# 5.net
KiCad netlist of a schematic drawn in Altium Designer
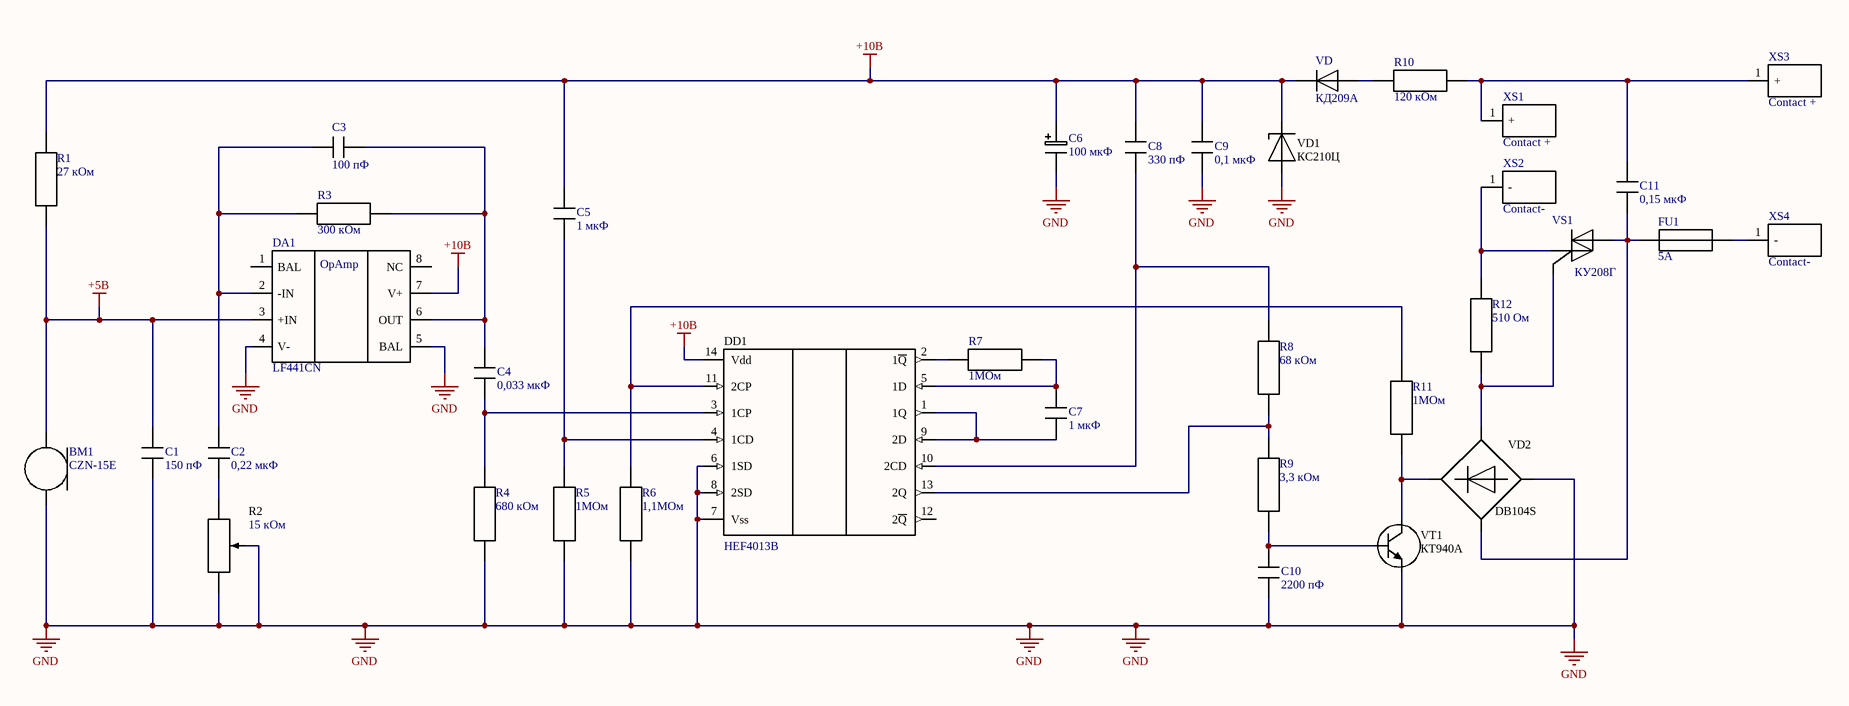
[diagram p0: 5 лист.SchDoc]

(export (version "E")
  (design (tool "Eeschema 10.0.6"))
  (components
    (comp (ref "BM1")
      (value "CZN-15E")
      (footprint "CZN-15E")
      (description "Microphone")
      (libsource (lib "Schlib1") (part "CZN-15E"))
    )
    (comp (ref "C1")
      (value "150 пФ")
      (footprint "CAP: 0805")
      (description "Capacitor Unpolarized")
      (fields (field (name "Comment") "CAP 0805 150 пФ"))
      (libsource (lib "Schlib1") (part "CAP 0805 150 пФ"))
    )
    (comp (ref "C2")
      (value "0,22 мкФ")
      (footprint "CAP: 0805")
      (description "Capacitor Unpolarized")
      (fields (field (name "Comment") "CAP 0805 0,22 мкФ"))
      (libsource (lib "Schlib1") (part "CAP 0805 0,22 мкФ"))
    )
    (comp (ref "C3")
      (value "100 пФ")
      (footprint "CAP: 0805")
      (description "Capacitor Unpolarized")
      (fields (field (name "Comment") "CAP 0805 100 пФ"))
      (libsource (lib "Schlib1") (part "CAP 0805 100 пФ"))
    )
    (comp (ref "C4")
      (value "0,033 мкФ")
      (footprint "CAP: 0805")
      (description "Capacitor Unpolarized")
      (fields (field (name "Comment") "CAP 0805 0,033 мкФ"))
      (libsource (lib "Schlib1") (part "CAP 0805 0,033 мкФ"))
    )
    (comp (ref "C5")
      (value "1 мкФ")
      (footprint "CAP: 0805")
      (description "Capacitor Unpolarized")
      (fields (field (name "Comment") "CAP 0805 1 мкФ"))
      (libsource (lib "Schlib1") (part "CAP 0805 1 мкФ"))
    )
    (comp (ref "C6")
      (value "100 мкФ")
      (footprint "ECAP 6,3x5.4мм")
      (description "Capacitor Polarized")
      (fields (field (name "Comment") "CAP 6,3X5.4 100 мкФ"))
      (libsource (lib "Schlib1") (part "CAP 6,3X5.4 100 мкФ"))
    )
    (comp (ref "C7")
      (value "1 мкФ")
      (footprint "CAP: 0805")
      (description "Capacitor Unpolarized")
      (fields (field (name "Comment") "CAP 0805 1 мкФ"))
      (libsource (lib "Schlib1") (part "CAP 0805 1 мкФ"))
    )
    (comp (ref "C8")
      (value "330 пФ")
      (footprint "CAP: 0805")
      (description "Capacitor Unpolarized")
      (fields (field (name "Comment") "CAP 0805 330 пФ"))
      (libsource (lib "Schlib1") (part "CAP 0805 330 пФ"))
    )
    (comp (ref "C9")
      (value "0,1 мкФ")
      (footprint "K73-17 B32521")
      (description "Capacitor Unpolarized")
      (fields (field (name "Comment") "CAP K73-17 0,1 мкФ"))
      (libsource (lib "Schlib1") (part "CAP K73-17 0,1 мкФ"))
    )
    (comp (ref "C10")
      (value "2200 пФ")
      (footprint "CAP: 0805")
      (description "Capacitor Unpolarized")
      (fields (field (name "Comment") "CAP 0805 2200 пФ"))
      (libsource (lib "Schlib1") (part "CAP 0805 2200 пФ"))
    )
    (comp (ref "C11")
      (value "0,15 мкФ")
      (footprint "CAP: 1206")
      (description "Capacitor Unpolarized")
      (fields (field (name "Comment") "CAP 1206 0,15 мкФ"))
      (libsource (lib "Schlib1") (part "CAP 1206 0,15 мкФ"))
    )
    (comp (ref "DA1")
      (value "LF441CN")
      (footprint "DIP8")
      (description "Amp Op")
      (libsource (lib "Schlib1") (part "LF441CN"))
    )
    (comp (ref "DD1")
      (value "HEF4013B")
      (footprint "DIP14")
      (description "D-Trigger")
      (fields (field (name "MANUFACTURER") "NXP"))
      (libsource (lib "Schlib1") (part "HEF4013B"))
    )
    (comp (ref "FU1")
      (value "5А")
      (footprint "FUSE 5A")
      (description "Fuse")
      (fields (field (name "Comment") "MF02S84-5000"))
      (libsource (lib "Schlib1") (part "MF02S84-5000"))
    )
    (comp (ref "R1")
      (value "27 кОм")
      (footprint "RES: 0805")
      (description "Resistor")
      (fields (field (name "Comment") "RES 0805 27 кОм"))
      (libsource (lib "Schlib1") (part "RES 0805 27 кОм"))
    )
    (comp (ref "R2")
      (value "15 кОм")
      (footprint "СП3-4АМ")
      (description "Potenciometr")
      (libsource (lib "Schlib1") (part "СП3-4М"))
    )
    (comp (ref "R3")
      (value "300 кОм")
      (footprint "RES: 0805")
      (description "Resistor")
      (fields (field (name "Comment") "RES 0805 300 кОм"))
      (libsource (lib "Schlib1") (part "RES 0805 300 кОм"))
    )
    (comp (ref "R4")
      (value "680 кОм")
      (footprint "RES: 0805")
      (description "Resistor")
      (fields (field (name "Comment") "RES 0805 680 кОм"))
      (libsource (lib "Schlib1") (part "RES 0805 680 кОм"))
    )
    (comp (ref "R5")
      (value "1МОм")
      (footprint "RES: 0805")
      (description "Resistor")
      (fields (field (name "Comment") "RES 0805 1МОм"))
      (libsource (lib "Schlib1") (part "RES 0805 1МОм"))
    )
    (comp (ref "R6")
      (value "1,1МОм")
      (footprint "RES: 0805")
      (description "Resistor")
      (fields (field (name "Comment") "RES 0805 1,1МОм"))
      (libsource (lib "Schlib1") (part "RES 0805 1,1МОм"))
    )
    (comp (ref "R7")
      (value "1МОм")
      (footprint "RES: 0805")
      (description "Resistor")
      (fields (field (name "Comment") "RES 0805 1МОм"))
      (libsource (lib "") (part "RES 0805 1МОм_1"))
    )
    (comp (ref "R8")
      (value "68 кОм")
      (footprint "RES: 0805")
      (description "Resistor")
      (fields (field (name "Comment") "RES 0805 68 кОм"))
      (libsource (lib "Schlib1") (part "RES 0805 68 кОм"))
    )
    (comp (ref "R9")
      (value "3,3 кОм")
      (footprint "RES: 0805")
      (description "Resistor")
      (fields (field (name "Comment") "RES 0805 3,3 кОм"))
      (libsource (lib "Schlib1") (part "RES 0805 3,3 кОм"))
    )
    (comp (ref "R10")
      (value "120 кОм")
      (footprint "RES: 1206")
      (description "Resistor")
      (fields (field (name "Comment") "RES 1206 120 кОм"))
      (libsource (lib "Schlib1") (part "RES 1206 120 кОм"))
    )
    (comp (ref "R11")
      (value "1МОм")
      (footprint "RES: 0805")
      (description "Resistor")
      (fields (field (name "Comment") "RES 1206 1МОм"))
      (libsource (lib "Schlib1") (part "RES 1206 1МОм"))
    )
    (comp (ref "R12")
      (value "510 Ом")
      (footprint "RES: 0805")
      (description "Resistor")
      (fields (field (name "Comment") "RES 0805 510 Ом"))
      (libsource (lib "Schlib1") (part "RES 0805 510 Ом"))
    )
    (comp (ref "VD")
      (value "КД209А")
      (footprint "DO-35")
      (description "Diode")
      (libsource (lib "Schlib1") (part "КД209А"))
    )
    (comp (ref "VD1")
      (value "КС210Ц")
      (footprint "DO-35")
      (description "Zener diode")
      (fields (field (name "MANUFACTURER") "Diodes Incorporated") (field (name "PARTNUMBER") "КС210Ц"))
      (libsource (lib "Schlib1") (part "КС210Ц"))
    )
    (comp (ref "VD2")
      (value "DB104S")
      (footprint "DB-1S")
      (description "Bridge Diode")
      (fields
        (field (name "MANUFACTURER") "Fairchhild Semiconductor Corporation")
        (field (name "PARTNUMBER") "DB104S")
      )
      (libsource (lib "Schlib1") (part "DB104S"))
    )
    (comp (ref "VS1")
      (value "КУ208Г")
      (footprint "TO-220")
      (description "Simistor")
      (libsource (lib "Schlib1") (part "КУ208Г"))
    )
    (comp (ref "VT1")
      (value "КТ940А")
      (footprint "TO-126")
      (description "Transistor NPN")
      (fields (field (name "MANUFACTURER") "ON Semiconductor") (field (name "PARTNUMBER") "КТ940А"))
      (libsource (lib "Schlib1") (part "КТ940А"))
    )
    (comp (ref "XS1")
      (value "Contact +")
      (footprint "CONTACT +")
      (description "Connector")
      (libsource (lib "Schlib1") (part "Contact +"))
    )
    (comp (ref "XS2")
      (value "Contact-")
      (footprint "CONTACT -")
      (description "Connector")
      (libsource (lib "Schlib1") (part "Contact-"))
    )
    (comp (ref "XS3")
      (value "Contact +")
      (footprint "CONTACT +")
      (description "Connector")
      (libsource (lib "Schlib1") (part "Contact +"))
    )
    (comp (ref "XS4")
      (value "Contact-")
      (footprint "CONTACT -")
      (description "Connector")
      (libsource (lib "Schlib1") (part "Contact-"))
    )
  )
  (nets
    (net (code "1") (name "+5В") (class "Default")
      (node (ref "BM1") (pin "1") (pinfunction "+_1") (pintype "passive"))
      (node (ref "C1") (pin "2") (pinfunction "2_2") (pintype "passive"))
      (node (ref "DA1") (pin "3") (pinfunction "+IN_3") (pintype "passive"))
      (node (ref "R1") (pin "1") (pinfunction "1_1") (pintype "passive"))
    )
    (net (code "2") (name "+10В") (class "Default")
      (node (ref "C5") (pin "2") (pinfunction "2_2") (pintype "passive"))
      (node (ref "C6") (pin "1") (pinfunction "1_1") (pintype "passive"))
      (node (ref "C8") (pin "2") (pinfunction "2_2") (pintype "passive"))
      (node (ref "C9") (pin "2") (pinfunction "2_2") (pintype "passive"))
      (node (ref "DA1") (pin "7") (pinfunction "V+_7") (pintype "passive"))
      (node (ref "DD1") (pin "14") (pinfunction "Vdd_14") (pintype "power_in"))
      (node (ref "R1") (pin "2") (pinfunction "2_2") (pintype "passive"))
      (node (ref "VD") (pin "2") (pinfunction "K_2") (pintype "passive"))
      (node (ref "VD1") (pin "2") (pinfunction "K_2") (pintype "passive"))
    )
    (net (code "3") (name "GND") (class "Default")
      (node (ref "BM1") (pin "2") (pinfunction "-_2") (pintype "passive"))
      (node (ref "C1") (pin "1") (pinfunction "1_1") (pintype "passive"))
      (node (ref "C10") (pin "1") (pinfunction "1_1") (pintype "passive"))
      (node (ref "C6") (pin "2") (pinfunction "2_2") (pintype "passive"))
      (node (ref "C9") (pin "1") (pinfunction "1_1") (pintype "passive"))
      (node (ref "DA1") (pin "4") (pinfunction "V-_4") (pintype "passive"))
      (node (ref "DA1") (pin "5") (pinfunction "BAL_5") (pintype "passive"))
      (node (ref "DD1") (pin "6") (pinfunction "1SD_6") (pintype "input"))
      (node (ref "DD1") (pin "7") (pinfunction "Vss_7") (pintype "power_in"))
      (node (ref "DD1") (pin "8") (pinfunction "2SD_8") (pintype "input"))
      (node (ref "R2") (pin "2") (pinfunction "2_2") (pintype "passive"))
      (node (ref "R2") (pin "3") (pinfunction "3_3") (pintype "passive"))
      (node (ref "R4") (pin "1") (pinfunction "1_1") (pintype "passive"))
      (node (ref "R5") (pin "1") (pinfunction "1_1") (pintype "passive"))
      (node (ref "R6") (pin "1") (pinfunction "1_1") (pintype "passive"))
      (node (ref "VD1") (pin "1") (pinfunction "A_1") (pintype "passive"))
      (node (ref "VD2") (pin "1") (pinfunction "-_1") (pintype "passive"))
      (node (ref "VT1") (pin "3") (pinfunction "E_3") (pintype "passive"))
    )
    (net (code "4") (name "Net-(C2-Pad1)") (class "Default")
      (node (ref "C2") (pin "1") (pinfunction "1_1") (pintype "passive"))
      (node (ref "R2") (pin "1") (pinfunction "1_1") (pintype "passive"))
    )
    (net (code "5") (name "Net-(DA1--IN)") (class "Default")
      (node (ref "C2") (pin "2") (pinfunction "2_2") (pintype "passive"))
      (node (ref "C3") (pin "1") (pinfunction "1_1") (pintype "passive"))
      (node (ref "DA1") (pin "2") (pinfunction "-IN_2") (pintype "passive"))
      (node (ref "R3") (pin "1") (pinfunction "1_1") (pintype "passive"))
    )
    (net (code "6") (name "Net-(DA1-OUT)") (class "Default")
      (node (ref "C3") (pin "2") (pinfunction "2_2") (pintype "passive"))
      (node (ref "C4") (pin "2") (pinfunction "2_2") (pintype "passive"))
      (node (ref "DA1") (pin "6") (pinfunction "OUT_6") (pintype "passive"))
      (node (ref "R3") (pin "2") (pinfunction "2_2") (pintype "passive"))
    )
    (net (code "7") (name "Net-(DD1-1CD)") (class "Default")
      (node (ref "C5") (pin "1") (pinfunction "1_1") (pintype "passive"))
      (node (ref "DD1") (pin "4") (pinfunction "1CD_4") (pintype "input"))
      (node (ref "R5") (pin "2") (pinfunction "2_2") (pintype "passive"))
    )
    (net (code "8") (name "Net-(DD1-1CP)") (class "Default")
      (node (ref "C4") (pin "1") (pinfunction "1_1") (pintype "passive"))
      (node (ref "DD1") (pin "3") (pinfunction "1CP_3") (pintype "input"))
      (node (ref "R4") (pin "2") (pinfunction "2_2") (pintype "passive"))
    )
    (net (code "9") (name "Net-(DD1-1D)") (class "Default")
      (node (ref "C7") (pin "1") (pinfunction "1_1") (pintype "passive"))
      (node (ref "DD1") (pin "5") (pinfunction "1D_5") (pintype "input"))
      (node (ref "R7") (pin "2") (pinfunction "2_2") (pintype "passive"))
    )
    (net (code "10") (name "Net-(DD1-1Q)") (class "Default")
      (node (ref "C7") (pin "2") (pinfunction "2_2") (pintype "passive"))
      (node (ref "DD1") (pin "1") (pinfunction "1Q_1") (pintype "output"))
      (node (ref "DD1") (pin "9") (pinfunction "2D_9") (pintype "input"))
    )
    (net (code "11") (name "Net-(DD1-1~{Q})") (class "Default")
      (node (ref "DD1") (pin "2") (pinfunction "1~{Q}_2") (pintype "output"))
      (node (ref "R7") (pin "1") (pinfunction "1_1") (pintype "passive"))
    )
    (net (code "12") (name "Net-(DD1-2CD)") (class "Default")
      (node (ref "C8") (pin "1") (pinfunction "1_1") (pintype "passive"))
      (node (ref "DD1") (pin "10") (pinfunction "2CD_10") (pintype "input"))
      (node (ref "R8") (pin "1") (pinfunction "1_1") (pintype "passive"))
    )
    (net (code "13") (name "Net-(DD1-2CP)") (class "Default")
      (node (ref "DD1") (pin "11") (pinfunction "2CP_11") (pintype "input"))
      (node (ref "R11") (pin "1") (pinfunction "1_1") (pintype "passive"))
      (node (ref "R6") (pin "2") (pinfunction "2_2") (pintype "passive"))
    )
    (net (code "14") (name "Net-(DD1-2Q)") (class "Default")
      (node (ref "DD1") (pin "13") (pinfunction "2Q_13") (pintype "output"))
      (node (ref "R8") (pin "2") (pinfunction "2_2") (pintype "passive"))
      (node (ref "R9") (pin "2") (pinfunction "2_2") (pintype "passive"))
    )
    (net (code "15") (name "Net-(VD-A)") (class "Default")
      (node (ref "R10") (pin "1") (pinfunction "1_1") (pintype "passive"))
      (node (ref "VD") (pin "1") (pinfunction "A_1") (pintype "passive"))
    )
    (net (code "16") (name "Net-(VD2-+)") (class "Default")
      (node (ref "R11") (pin "2") (pinfunction "2_2") (pintype "passive"))
      (node (ref "VD2") (pin "3") (pinfunction "+_3") (pintype "passive"))
      (node (ref "VT1") (pin "2") (pinfunction "C_2") (pintype "passive"))
    )
    (net (code "17") (name "Net-(VS1-G)") (class "Default")
      (node (ref "R12") (pin "1") (pinfunction "1_1") (pintype "passive"))
      (node (ref "VD2") (pin "4") (pinfunction "~_4") (pintype "passive"))
      (node (ref "VS1") (pin "3") (pinfunction "G_3") (pintype "passive"))
    )
    (net (code "18") (name "Net-(VS1-T1)") (class "Default")
      (node (ref "C11") (pin "1") (pinfunction "1_1") (pintype "passive"))
      (node (ref "FU1") (pin "1") (pinfunction "1_1") (pintype "passive"))
      (node (ref "VD2") (pin "2") (pinfunction "~_2") (pintype "passive"))
      (node (ref "VS1") (pin "1") (pinfunction "T1_1") (pintype "passive"))
    )
    (net (code "19") (name "Net-(VS1-T2)") (class "Default")
      (node (ref "R12") (pin "2") (pinfunction "2_2") (pintype "passive"))
      (node (ref "VS1") (pin "2") (pinfunction "T2_2") (pintype "passive"))
      (node (ref "XS2") (pin "1") (pinfunction "-_1") (pintype "passive"))
    )
    (net (code "20") (name "Net-(VT1-B)") (class "Default")
      (node (ref "C10") (pin "2") (pinfunction "2_2") (pintype "passive"))
      (node (ref "R9") (pin "1") (pinfunction "1_1") (pintype "passive"))
      (node (ref "VT1") (pin "1") (pinfunction "B_1") (pintype "passive"))
    )
    (net (code "21") (name "Net-(XS1-+)") (class "Default")
      (node (ref "C11") (pin "2") (pinfunction "2_2") (pintype "passive"))
      (node (ref "R10") (pin "2") (pinfunction "2_2") (pintype "passive"))
      (node (ref "XS1") (pin "1") (pinfunction "+_1") (pintype "passive"))
      (node (ref "XS3") (pin "1") (pinfunction "+_1") (pintype "passive"))
    )
    (net (code "22") (name "Net-(XS4--)") (class "Default")
      (node (ref "FU1") (pin "2") (pinfunction "2_2") (pintype "passive"))
      (node (ref "XS4") (pin "1") (pinfunction "-_1") (pintype "passive"))
    )
    (net (code "23") (name "unconnected-(DA1-BAL-Pad1)") (class "Default")
      (node (ref "DA1") (pin "1") (pinfunction "BAL_1") (pintype "passive"))
    )
    (net (code "24") (name "unconnected-(DA1-NC-Pad8)") (class "Default")
      (node (ref "DA1") (pin "8") (pinfunction "NC_8") (pintype "passive"))
    )
    (net (code "25") (name "unconnected-(DD1-2~{Q}-Pad12)") (class "Default")
      (node (ref "DD1") (pin "12") (pinfunction "2~{Q}_12") (pintype "output"))
    )
  )
)
